# Girlfriend_Tracker_V0_2.net
KiCad netlist of a schematic drawn in EAGLE
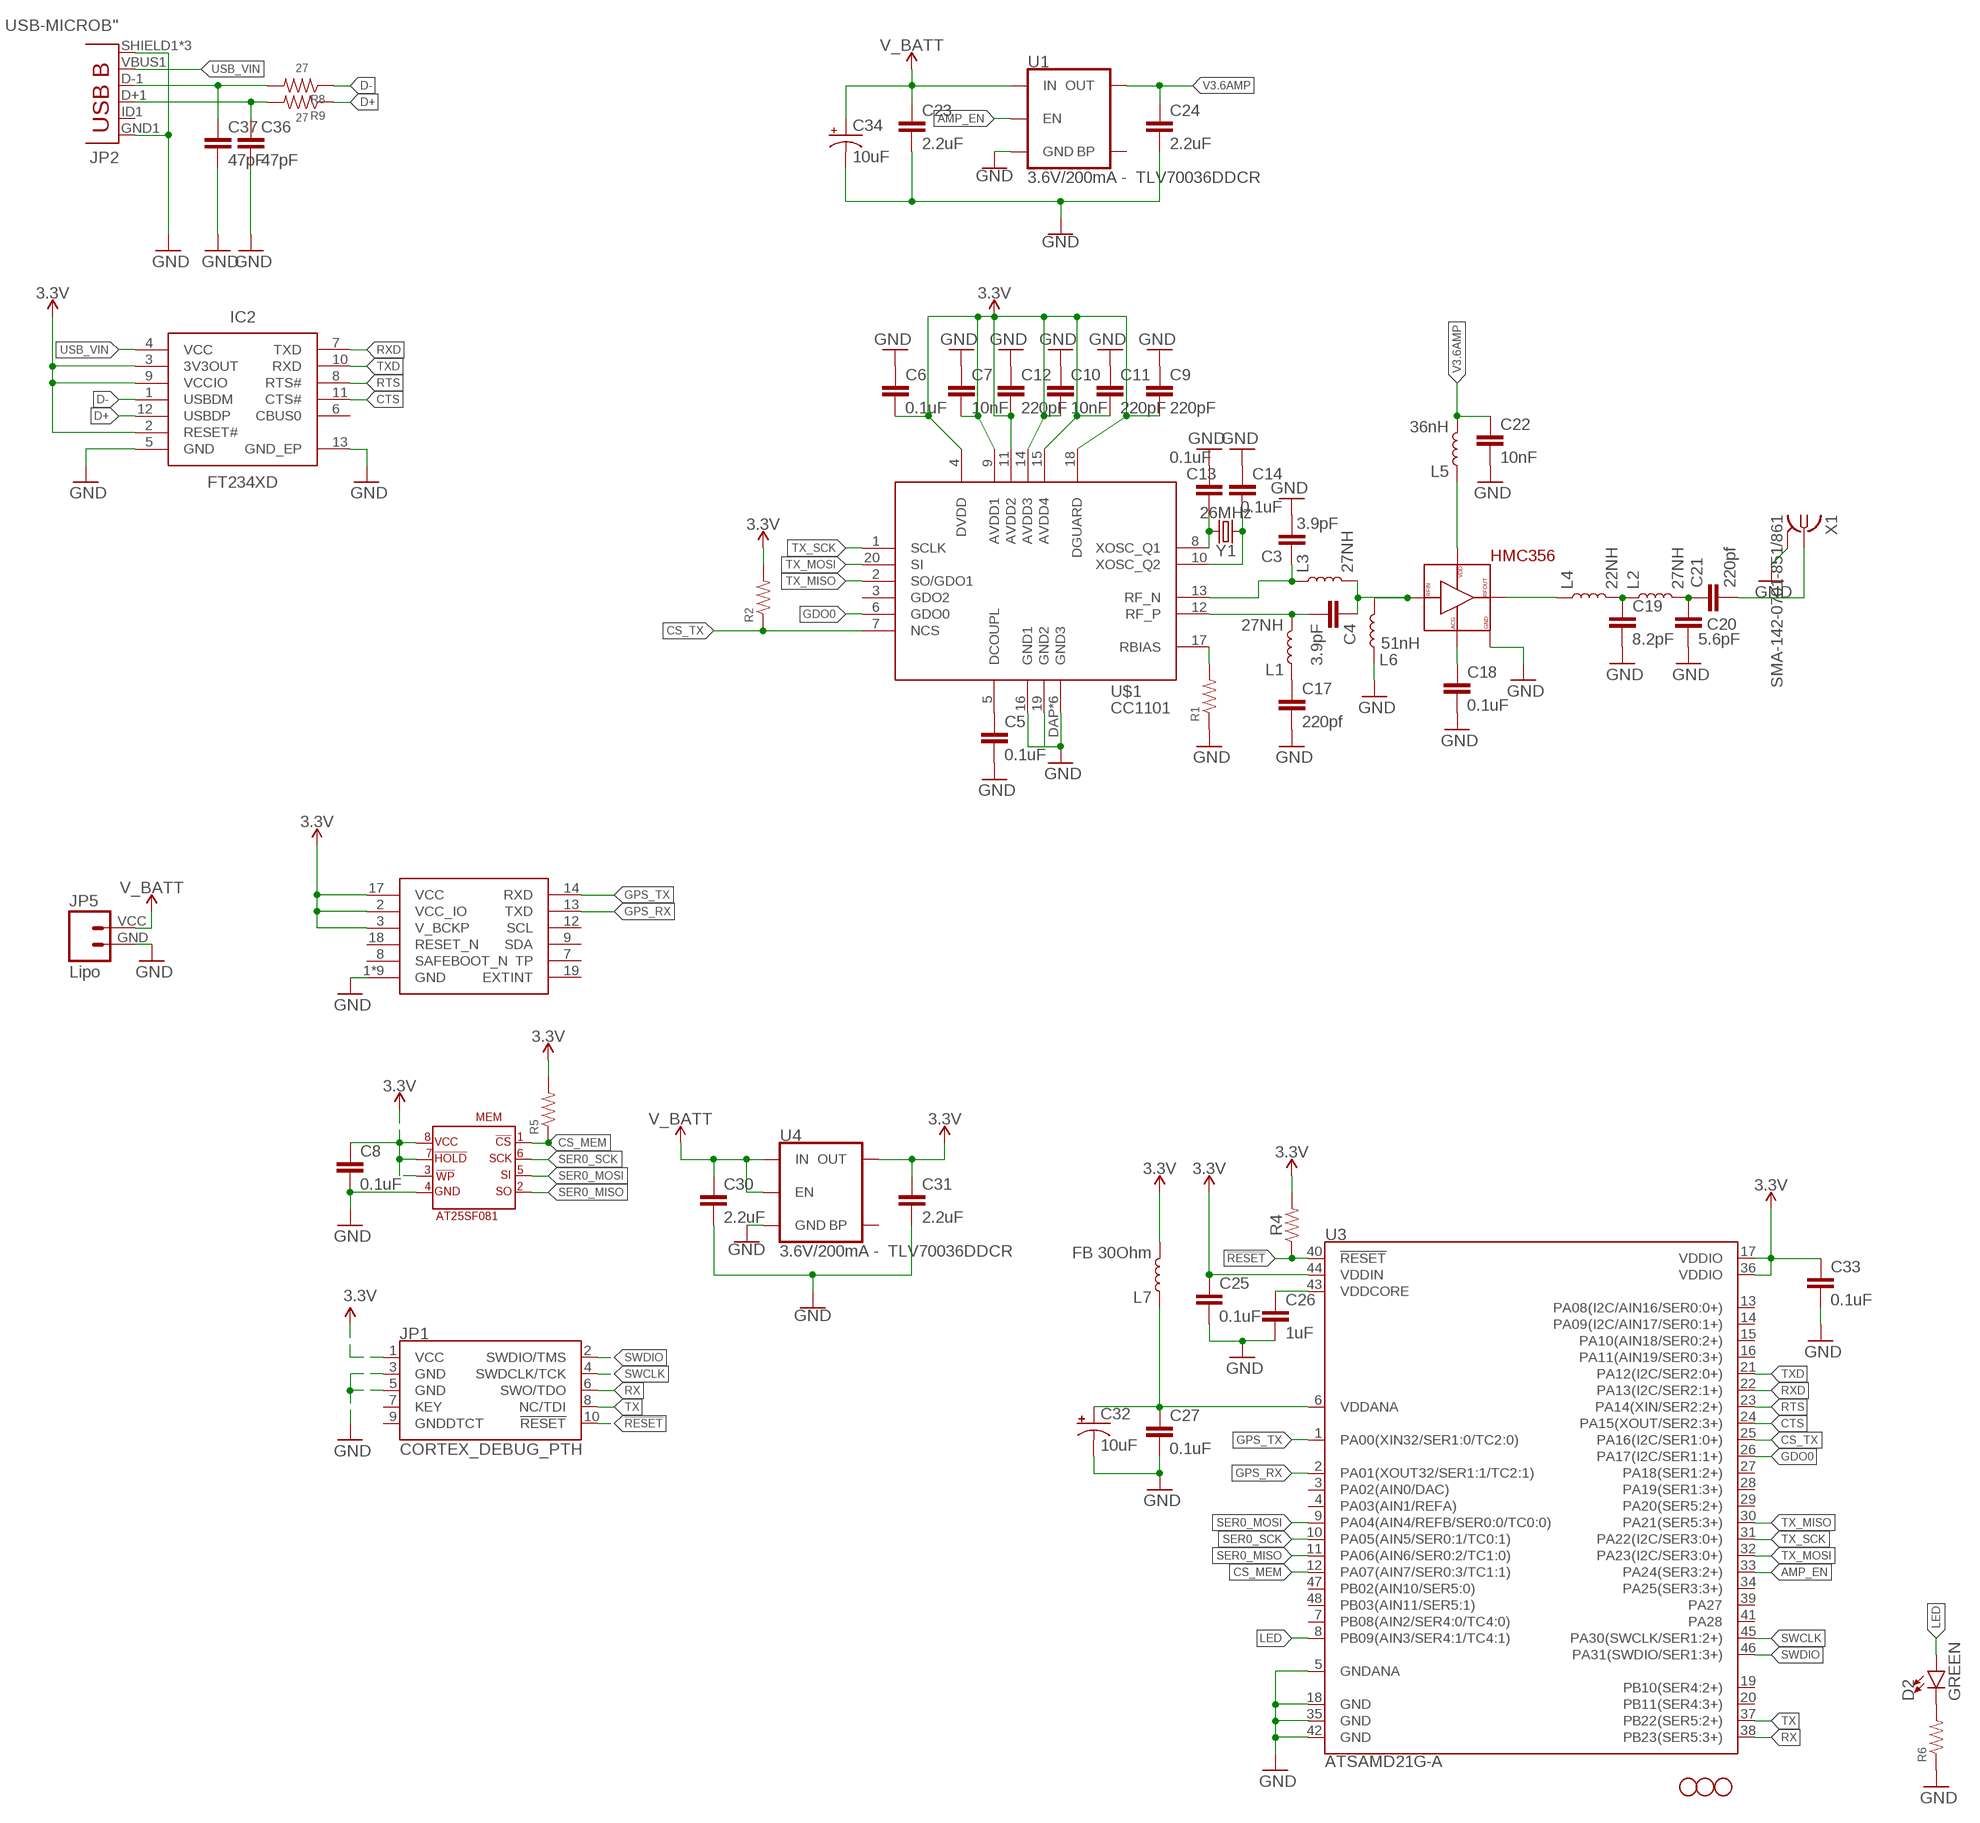
[diagram p0: schematic, sheet 1]

(export (version "E")
  (design (tool "Eeschema 10.0.6"))
  (components
    (comp (ref "C3")
      (value "3.9pF")
      (footprint "eagle-import:0402")
      (libsource (lib "eagle-import") (part "0.1UF-0402-16V-10%"))
    )
    (comp (ref "C4")
      (value "3.9pF")
      (footprint "eagle-import:0402")
      (libsource (lib "eagle-import") (part "0.1UF-0402-16V-10%"))
    )
    (comp (ref "C5")
      (value "0.1uF")
      (footprint "eagle-import:0402")
      (libsource (lib "eagle-import") (part "0.1UF-0402-16V-10%"))
    )
    (comp (ref "C6")
      (value "0.1uF")
      (footprint "eagle-import:0402")
      (libsource (lib "eagle-import") (part "0.1UF-0402-16V-10%"))
    )
    (comp (ref "C7")
      (value "10nF")
      (footprint "eagle-import:0402")
      (libsource (lib "eagle-import") (part "0.1UF-0402-16V-10%"))
    )
    (comp (ref "C8")
      (value "0.1uF")
      (footprint "eagle-import:0402")
      (libsource (lib "eagle-import") (part "0.1UF-0402-16V-10%"))
    )
    (comp (ref "C9")
      (value "220pF")
      (footprint "eagle-import:0402")
      (libsource (lib "eagle-import") (part "0.1UF-0402-16V-10%"))
    )
    (comp (ref "C10")
      (value "10nF")
      (footprint "eagle-import:0402")
      (libsource (lib "eagle-import") (part "0.1UF-0402-16V-10%"))
    )
    (comp (ref "C11")
      (value "220pF")
      (footprint "eagle-import:0402")
      (libsource (lib "eagle-import") (part "0.1UF-0402-16V-10%"))
    )
    (comp (ref "C12")
      (value "220pF")
      (footprint "eagle-import:0402")
      (libsource (lib "eagle-import") (part "0.1UF-0402-16V-10%"))
    )
    (comp (ref "C13")
      (value "0.1uF")
      (footprint "eagle-import:0402")
      (libsource (lib "eagle-import") (part "0.1UF-0402-16V-10%"))
    )
    (comp (ref "C14")
      (value "0.1uF")
      (footprint "eagle-import:0402")
      (libsource (lib "eagle-import") (part "0.1UF-0402-16V-10%"))
    )
    (comp (ref "C17")
      (value "220pf")
      (footprint "eagle-import:0402")
      (libsource (lib "eagle-import") (part "0.1UF-0402-16V-10%"))
    )
    (comp (ref "C18")
      (value "0.1uF")
      (footprint "eagle-import:0402")
      (libsource (lib "eagle-import") (part "0.1UF-0402-16V-10%"))
    )
    (comp (ref "C19")
      (value "8.2pF")
      (footprint "eagle-import:0402")
      (libsource (lib "eagle-import") (part "0.1UF-0402-16V-10%"))
    )
    (comp (ref "C20")
      (value "5.6pF")
      (footprint "eagle-import:0402")
      (libsource (lib "eagle-import") (part "0.1UF-0402-16V-10%"))
    )
    (comp (ref "C21")
      (value "220pf")
      (footprint "eagle-import:0402")
      (libsource (lib "eagle-import") (part "0.1UF-0402-16V-10%"))
    )
    (comp (ref "C22")
      (value "10nF")
      (footprint "eagle-import:0402")
      (libsource (lib "eagle-import") (part "0.1UF-0402-16V-10%"))
    )
    (comp (ref "C23")
      (value "2.2uF")
      (footprint "eagle-import:0603")
      (libsource (lib "eagle-import") (part "2.2UF-0603-10V-20%"))
    )
    (comp (ref "C24")
      (value "2.2uF")
      (footprint "eagle-import:0603")
      (libsource (lib "eagle-import") (part "2.2UF-0603-10V-20%"))
    )
    (comp (ref "C25")
      (value "0.1uF")
      (footprint "eagle-import:0402")
      (libsource (lib "eagle-import") (part "0.1UF-0402-16V-10%"))
    )
    (comp (ref "C26")
      (value "1uF")
      (footprint "eagle-import:0402")
      (libsource (lib "eagle-import") (part "0.1UF-0402-16V-10%"))
    )
    (comp (ref "C27")
      (value "0.1uF")
      (footprint "eagle-import:0402")
      (libsource (lib "eagle-import") (part "0.1UF-0402-16V-10%"))
    )
    (comp (ref "C30")
      (value "2.2uF")
      (footprint "eagle-import:0603")
      (libsource (lib "eagle-import") (part "2.2UF-0603-10V-20%"))
    )
    (comp (ref "C31")
      (value "2.2uF")
      (footprint "eagle-import:0603")
      (libsource (lib "eagle-import") (part "2.2UF-0603-10V-20%"))
    )
    (comp (ref "C32")
      (value "10uF")
      (footprint "eagle-import:EIA3216")
      (libsource (lib "eagle-import") (part "CAP_POL1206"))
    )
    (comp (ref "C33")
      (value "0.1uF")
      (footprint "eagle-import:0402")
      (libsource (lib "eagle-import") (part "0.1UF-0402-16V-10%"))
    )
    (comp (ref "C34")
      (value "10uF")
      (footprint "eagle-import:EIA3216")
      (libsource (lib "eagle-import") (part "CAP_POL1206"))
    )
    (comp (ref "C36")
      (value "47pF")
      (footprint "eagle-import:0402")
      (libsource (lib "eagle-import") (part "0.1UF-0402-16V-10%"))
    )
    (comp (ref "C37")
      (value "47pF")
      (footprint "eagle-import:0402")
      (libsource (lib "eagle-import") (part "0.1UF-0402-16V-10%"))
    )
    (comp (ref "D2")
      (value "GREEN")
      (footprint "eagle-import:LED-1206")
      (libsource (lib "eagle-import") (part "LED-GREEN1206"))
    )
    (comp (ref "H1")
      (value "STAND-OFFTIGHT")
      (footprint "eagle-import:STAND-OFF-TIGHT")
      (libsource (lib "eagle-import") (part "STAND-OFFTIGHT"))
    )
    (comp (ref "H2")
      (value "STAND-OFFTIGHT")
      (footprint "eagle-import:STAND-OFF-TIGHT")
      (libsource (lib "eagle-import") (part "STAND-OFFTIGHT"))
    )
    (comp (ref "H3")
      (value "STAND-OFFTIGHT")
      (footprint "eagle-import:STAND-OFF-TIGHT")
      (libsource (lib "eagle-import") (part "STAND-OFFTIGHT"))
    )
    (comp (ref "IC1")
      (value "SAM-M8Q")
      (footprint "eagle-import:SAM-M8Q")
      (libsource (lib "eagle-import") (part "SAM-M8Q"))
    )
    (comp (ref "IC2")
      (value "FT234XD")
      (footprint "eagle-import:SON45P300X300X80-13N")
      (fields (field (name "MANUFACTURER_PART_NUMBER") "ft234xd"))
      (libsource (lib "eagle-import") (part "FT234XD"))
    )
    (comp (ref "JP1")
      (value "CORTEX_DEBUG_PTH")
      (footprint "eagle-import:2X5-PTH-1.27MM")
      (libsource (lib "eagle-import") (part "CORTEX_DEBUG_PTH"))
    )
    (comp (ref "JP2")
      (value "USB-MICROB\"")
      (footprint "eagle-import:USB-B-MICRO-SMD_V03")
      (libsource (lib "eagle-import") (part "USB-MICROB{dblquote}"))
    )
    (comp (ref "JP5")
      (value "Lipo")
      (footprint "eagle-import:JST-2-SMD-VERT")
      (libsource (lib "eagle-import") (part "M024UCON-15767"))
    )
    (comp (ref "L1")
      (value "27NH")
      (footprint "eagle-import:0402")
      (libsource (lib "eagle-import") (part "SparkFun-Coils_512_INDUCTOR-0402-3.9NH"))
    )
    (comp (ref "L2")
      (value "27NH")
      (footprint "eagle-import:0402")
      (libsource (lib "eagle-import") (part "SparkFun-Coils_512_INDUCTOR-0402-3.9NH"))
    )
    (comp (ref "L3")
      (value "27NH")
      (footprint "eagle-import:0402")
      (libsource (lib "eagle-import") (part "SparkFun-Coils_512_INDUCTOR-0402-3.9NH"))
    )
    (comp (ref "L4")
      (value "22NH")
      (footprint "eagle-import:0402")
      (libsource (lib "eagle-import") (part "SparkFun-Coils_512_INDUCTOR-0402-3.9NH"))
    )
    (comp (ref "L5")
      (value "36nH")
      (footprint "eagle-import:0402")
      (libsource (lib "eagle-import") (part "SparkFun-Coils_512_INDUCTOR-0402-3.9NH"))
    )
    (comp (ref "L6")
      (value "51nH")
      (footprint "eagle-import:0402")
      (libsource (lib "eagle-import") (part "SparkFun-Coils_512_INDUCTOR-0402-3.9NH"))
    )
    (comp (ref "L7")
      (value "FB 30Ohm")
      (footprint "eagle-import:0603")
      (libsource (lib "eagle-import") (part "INDUCTOR-0603-33NH"))
    )
    (comp (ref "MEM")
      (value "AT25SF081")
      (footprint "eagle-import:AT25SF081")
      (libsource (lib "eagle-import") (part "AT25SF081"))
    )
    (comp (ref "R1")
      (value "RESISTOR0402")
      (footprint "eagle-import:0402")
      (libsource (lib "eagle-import") (part "RESISTOR0402"))
    )
    (comp (ref "R2")
      (value "RESISTOR0402")
      (footprint "eagle-import:0402")
      (libsource (lib "eagle-import") (part "RESISTOR0402"))
    )
    (comp (ref "R4")
      (value "RESISTOR0402")
      (footprint "eagle-import:0402")
      (libsource (lib "eagle-import") (part "RESISTOR0402"))
    )
    (comp (ref "R5")
      (value "RESISTOR0402")
      (footprint "eagle-import:0402")
      (libsource (lib "eagle-import") (part "RESISTOR0402"))
    )
    (comp (ref "R6")
      (value "RESISTOR0402")
      (footprint "eagle-import:0402")
      (libsource (lib "eagle-import") (part "RESISTOR0402"))
    )
    (comp (ref "R8")
      (value "27")
      (footprint "eagle-import:0402")
      (libsource (lib "eagle-import") (part "RESISTOR0402"))
    )
    (comp (ref "R9")
      (value "27")
      (footprint "eagle-import:0402")
      (libsource (lib "eagle-import") (part "RESISTOR0402"))
    )
    (comp (ref "U$1")
      (value "CC1101")
      (footprint "eagle-import:CC1101")
      (libsource (lib "eagle-import") (part "CC1101"))
    )
    (comp (ref "U$3")
      (value "HMC356")
      (footprint "eagle-import:QFN16_HMC356")
      (libsource (lib "eagle-import") (part "HMC356"))
    )
    (comp (ref "U1")
      (value "3.6V/200mA - TLV70036DDCR")
      (footprint "eagle-import:SOT23-5")
      (libsource (lib "eagle-import") (part "V_REG_MIC52053.3V"))
    )
    (comp (ref "U3")
      (value "ATSAMD21G-A")
      (footprint "eagle-import:TQFP-48")
      (libsource (lib "eagle-import") (part "ATSAMD21G-A"))
    )
    (comp (ref "U4")
      (value "3.6V/200mA - TLV70036DDCR")
      (footprint "eagle-import:SOT23-5")
      (libsource (lib "eagle-import") (part "V_REG_MIC52053.3V"))
    )
    (comp (ref "X1")
      (value "SMA-142-0701-851/861")
      (footprint "eagle-import:J502-ND-142-0701-851_861")
      (fields (field (name "MF") "JOHNSON COMPONENTS") (field (name "MPN") "142-0701-851"))
      (libsource (lib "eagle-import") (part "SMA-142-0701-851/861"))
    )
    (comp (ref "Y1")
      (value "26MHz")
      (footprint "eagle-import:CRYSTAL-SMD-3.2X2.5MM")
      (libsource (lib "eagle-import") (part "CRYSTALSMD-3.2X2.5"))
    )
  )
  (nets
    (net (code "1") (name "/~{RESET}") (class "Default")
      (node (ref "JP1") (pin "10") (pinfunction "~{RESET}_10") (pintype "bidirectional"))
      (node (ref "R4") (pin "1") (pinfunction "1_1") (pintype "passive"))
      (node (ref "U3") (pin "40") (pinfunction "~{RESET}_40") (pintype "bidirectional"))
    )
    (net (code "2") (name "3.3V") (class "Default")
      (node (ref "C10") (pin "2") (pinfunction "2_2") (pintype "passive"))
      (node (ref "C11") (pin "2") (pinfunction "2_2") (pintype "passive"))
      (node (ref "C12") (pin "2") (pinfunction "2_2") (pintype "passive"))
      (node (ref "C25") (pin "1") (pinfunction "1_1") (pintype "passive"))
      (node (ref "C31") (pin "1") (pinfunction "1_1") (pintype "passive"))
      (node (ref "C33") (pin "1") (pinfunction "1_1") (pintype "passive"))
      (node (ref "C6") (pin "2") (pinfunction "2_2") (pintype "passive"))
      (node (ref "C7") (pin "2") (pinfunction "2_2") (pintype "passive"))
      (node (ref "C8") (pin "1") (pinfunction "1_1") (pintype "passive"))
      (node (ref "C9") (pin "2") (pinfunction "2_2") (pintype "passive"))
      (node (ref "IC1") (pin "17") (pinfunction "VCC_17") (pintype "bidirectional"))
      (node (ref "IC1") (pin "2") (pinfunction "VCC_IO_2") (pintype "bidirectional"))
      (node (ref "IC1") (pin "3") (pinfunction "V_BCKP_3") (pintype "bidirectional"))
      (node (ref "IC2") (pin "2") (pinfunction "RESET#_2") (pintype "passive"))
      (node (ref "IC2") (pin "3") (pinfunction "3V3OUT_3") (pintype "output"))
      (node (ref "IC2") (pin "9") (pinfunction "VCCIO_9") (pintype "power_in"))
      (node (ref "JP1") (pin "1") (pinfunction "VCC_1") (pintype "bidirectional"))
      (node (ref "L7") (pin "2") (pinfunction "2_2") (pintype "passive"))
      (node (ref "MEM") (pin "!HOLD") (pinfunction "~{HOLD}_!HOLD") (pintype "bidirectional"))
      (node (ref "MEM") (pin "!WP") (pinfunction "~{WP}_!WP") (pintype "bidirectional"))
      (node (ref "MEM") (pin "VCC") (pinfunction "VCC_VCC") (pintype "bidirectional"))
      (node (ref "R2") (pin "2") (pinfunction "2_2") (pintype "passive"))
      (node (ref "R4") (pin "2") (pinfunction "2_2") (pintype "passive"))
      (node (ref "R5") (pin "2") (pinfunction "2_2") (pintype "passive"))
      (node (ref "U$1") (pin "11") (pinfunction "AVDD2_11") (pintype "bidirectional"))
      (node (ref "U$1") (pin "14") (pinfunction "AVDD3_14") (pintype "bidirectional"))
      (node (ref "U$1") (pin "15") (pinfunction "AVDD4_15") (pintype "bidirectional"))
      (node (ref "U$1") (pin "18") (pinfunction "DGUARD_18") (pintype "bidirectional"))
      (node (ref "U$1") (pin "4") (pinfunction "DVDD_4") (pintype "bidirectional"))
      (node (ref "U$1") (pin "9") (pinfunction "AVDD1_9") (pintype "bidirectional"))
      (node (ref "U3") (pin "17") (pinfunction "VDDIO_17") (pintype "bidirectional"))
      (node (ref "U3") (pin "36") (pinfunction "VDDIO_36") (pintype "bidirectional"))
      (node (ref "U3") (pin "44") (pinfunction "VDDIN_44") (pintype "bidirectional"))
      (node (ref "U4") (pin "5") (pinfunction "OUT_5") (pintype "passive"))
    )
    (net (code "3") (name "AMP_EN") (class "Default")
      (node (ref "U1") (pin "3") (pinfunction "EN_3") (pintype "input"))
      (node (ref "U3") (pin "33") (pinfunction "PA24(SER3:2+)_33") (pintype "bidirectional"))
    )
    (net (code "4") (name "CS_MEM") (class "Default")
      (node (ref "MEM") (pin "!CS") (pinfunction "~{CS}_!CS") (pintype "bidirectional"))
      (node (ref "R5") (pin "1") (pinfunction "1_1") (pintype "passive"))
      (node (ref "U3") (pin "12") (pinfunction "PA07(AIN7/SER0:3/TC1:1)_12") (pintype "bidirectional"))
    )
    (net (code "5") (name "CS_TX") (class "Default")
      (node (ref "R2") (pin "1") (pinfunction "1_1") (pintype "passive"))
      (node (ref "U$1") (pin "7") (pinfunction "NCS_7") (pintype "bidirectional"))
      (node (ref "U3") (pin "25") (pinfunction "PA16(I2C/SER1:0+)_25") (pintype "bidirectional"))
    )
    (net (code "6") (name "CTS") (class "Default")
      (node (ref "IC2") (pin "11") (pinfunction "CTS#_11") (pintype "passive"))
      (node (ref "U3") (pin "24") (pinfunction "PA15(XOUT/SER2:3+)_24") (pintype "bidirectional"))
    )
    (net (code "7") (name "D+") (class "Default")
      (node (ref "IC2") (pin "12") (pinfunction "USBDP_12") (pintype "passive"))
      (node (ref "R9") (pin "1") (pinfunction "1_1") (pintype "passive"))
    )
    (net (code "8") (name "D-") (class "Default")
      (node (ref "IC2") (pin "1") (pinfunction "USBDM_1") (pintype "passive"))
      (node (ref "R8") (pin "1") (pinfunction "1_1") (pintype "passive"))
    )
    (net (code "9") (name "GDO0") (class "Default")
      (node (ref "U$1") (pin "6") (pinfunction "GDO0_6") (pintype "bidirectional"))
      (node (ref "U3") (pin "26") (pinfunction "PA17(I2C/SER1:1+)_26") (pintype "bidirectional"))
    )
    (net (code "10") (name "GND") (class "Default")
      (node (ref "C10") (pin "1") (pinfunction "1_1") (pintype "passive"))
      (node (ref "C11") (pin "1") (pinfunction "1_1") (pintype "passive"))
      (node (ref "C12") (pin "1") (pinfunction "1_1") (pintype "passive"))
      (node (ref "C13") (pin "1") (pinfunction "1_1") (pintype "passive"))
      (node (ref "C14") (pin "2") (pinfunction "2_2") (pintype "passive"))
      (node (ref "C17") (pin "2") (pinfunction "2_2") (pintype "passive"))
      (node (ref "C18") (pin "2") (pinfunction "2_2") (pintype "passive"))
      (node (ref "C19") (pin "2") (pinfunction "2_2") (pintype "passive"))
      (node (ref "C20") (pin "2") (pinfunction "2_2") (pintype "passive"))
      (node (ref "C22") (pin "2") (pinfunction "2_2") (pintype "passive"))
      (node (ref "C23") (pin "2") (pinfunction "2_2") (pintype "passive"))
      (node (ref "C24") (pin "2") (pinfunction "2_2") (pintype "passive"))
      (node (ref "C25") (pin "2") (pinfunction "2_2") (pintype "passive"))
      (node (ref "C26") (pin "2") (pinfunction "2_2") (pintype "passive"))
      (node (ref "C27") (pin "2") (pinfunction "2_2") (pintype "passive"))
      (node (ref "C3") (pin "2") (pinfunction "2_2") (pintype "passive"))
      (node (ref "C30") (pin "2") (pinfunction "2_2") (pintype "passive"))
      (node (ref "C31") (pin "2") (pinfunction "2_2") (pintype "passive"))
      (node (ref "C32") (pin "C") (pinfunction "-_C") (pintype "passive"))
      (node (ref "C33") (pin "2") (pinfunction "2_2") (pintype "passive"))
      (node (ref "C34") (pin "C") (pinfunction "-_C") (pintype "passive"))
      (node (ref "C36") (pin "2") (pinfunction "2_2") (pintype "passive"))
      (node (ref "C37") (pin "2") (pinfunction "2_2") (pintype "passive"))
      (node (ref "C5") (pin "2") (pinfunction "2_2") (pintype "passive"))
      (node (ref "C6") (pin "1") (pinfunction "1_1") (pintype "passive"))
      (node (ref "C7") (pin "1") (pinfunction "1_1") (pintype "passive"))
      (node (ref "C8") (pin "2") (pinfunction "2_2") (pintype "passive"))
      (node (ref "C9") (pin "1") (pinfunction "1_1") (pintype "passive"))
      (node (ref "IC1") (pin "1") (pinfunction "GND_1") (pintype "bidirectional"))
      (node (ref "IC1") (pin "10") (pinfunction "GND_10") (pintype "bidirectional"))
      (node (ref "IC1") (pin "11") (pinfunction "GND_11") (pintype "bidirectional"))
      (node (ref "IC1") (pin "15") (pinfunction "GND_15") (pintype "bidirectional"))
      (node (ref "IC1") (pin "16") (pinfunction "GND_16") (pintype "bidirectional"))
      (node (ref "IC1") (pin "20") (pinfunction "GND_20") (pintype "bidirectional"))
      (node (ref "IC1") (pin "4") (pinfunction "GND_4") (pintype "bidirectional"))
      (node (ref "IC1") (pin "5") (pinfunction "GND_5") (pintype "bidirectional"))
      (node (ref "IC1") (pin "6") (pinfunction "GND_6") (pintype "bidirectional"))
      (node (ref "IC2") (pin "13") (pinfunction "GND_EP_13") (pintype "power_in"))
      (node (ref "IC2") (pin "5") (pinfunction "GND_5") (pintype "power_in"))
      (node (ref "JP1") (pin "3") (pinfunction "GND_3") (pintype "bidirectional"))
      (node (ref "JP1") (pin "5") (pinfunction "GND_5") (pintype "bidirectional"))
      (node (ref "JP2") (pin "GND1") (pinfunction "GND_GND1") (pintype "bidirectional"))
      (node (ref "JP2") (pin "SHIELD1") (pinfunction "SHIELD_SHIELD1") (pintype "bidirectional"))
      (node (ref "JP2") (pin "SHIELD2") (pinfunction "SHIELD_SHIELD2") (pintype "bidirectional"))
      (node (ref "JP2") (pin "SHIELD3") (pinfunction "SHIELD_SHIELD3") (pintype "bidirectional"))
      (node (ref "JP5") (pin "GND") (pinfunction "1_GND") (pintype "passive"))
      (node (ref "L6") (pin "1") (pinfunction "1_1") (pintype "passive"))
      (node (ref "MEM") (pin "GND") (pinfunction "GND_GND") (pintype "bidirectional"))
      (node (ref "R1") (pin "1") (pinfunction "1_1") (pintype "passive"))
      (node (ref "R6") (pin "1") (pinfunction "1_1") (pintype "passive"))
      (node (ref "U$1") (pin "16") (pinfunction "GND1_16") (pintype "bidirectional"))
      (node (ref "U$1") (pin "19") (pinfunction "GND2_19") (pintype "bidirectional"))
      (node (ref "U$1") (pin "DAP") (pinfunction "GND3_DAP") (pintype "bidirectional"))
      (node (ref "U$1") (pin "P$1") (pinfunction "GND3_P$1") (pintype "bidirectional"))
      (node (ref "U$1") (pin "P$2") (pinfunction "GND3_P$2") (pintype "bidirectional"))
      (node (ref "U$1") (pin "P$3") (pinfunction "GND3_P$3") (pintype "bidirectional"))
      (node (ref "U$1") (pin "P$4") (pinfunction "GND3_P$4") (pintype "bidirectional"))
      (node (ref "U$1") (pin "P$5") (pinfunction "GND3_P$5") (pintype "bidirectional"))
      (node (ref "U$3") (pin "P$16") (pinfunction "P$5_P$16") (pintype "bidirectional"))
      (node (ref "U$3") (pin "P$17") (pinfunction "P$5_P$17") (pintype "bidirectional"))
      (node (ref "U$3") (pin "P$17_1") (pinfunction "P$5_P$17_1") (pintype "bidirectional"))
      (node (ref "U$3") (pin "P$17_2") (pinfunction "P$5_P$17_2") (pintype "bidirectional"))
      (node (ref "U$3") (pin "P$17_3") (pinfunction "P$5_P$17_3") (pintype "bidirectional"))
      (node (ref "U$3") (pin "P$17_4") (pinfunction "P$5_P$17_4") (pintype "bidirectional"))
      (node (ref "U$3") (pin "P$2") (pinfunction "P$5_P$2") (pintype "bidirectional"))
      (node (ref "U$3") (pin "P$4") (pinfunction "P$5_P$4") (pintype "bidirectional"))
      (node (ref "U$3") (pin "P$6") (pinfunction "P$5_P$6") (pintype "bidirectional"))
      (node (ref "U1") (pin "2") (pinfunction "GND_2") (pintype "input"))
      (node (ref "U3") (pin "18") (pinfunction "GND_18") (pintype "bidirectional"))
      (node (ref "U3") (pin "35") (pinfunction "GND_35") (pintype "bidirectional"))
      (node (ref "U3") (pin "42") (pinfunction "GND_42") (pintype "bidirectional"))
      (node (ref "U3") (pin "5") (pinfunction "GNDANA_5") (pintype "bidirectional"))
      (node (ref "U4") (pin "2") (pinfunction "GND_2") (pintype "input"))
      (node (ref "X1") (pin "G@1") (pinfunction "2_G@1") (pintype "passive"))
      (node (ref "X1") (pin "G@2") (pinfunction "2_G@2") (pintype "passive"))
      (node (ref "X1") (pin "G@3") (pinfunction "2_G@3") (pintype "passive"))
      (node (ref "X1") (pin "G@4") (pinfunction "2_G@4") (pintype "passive"))
    )
    (net (code "11") (name "GPS_RX") (class "Default")
      (node (ref "IC1") (pin "13") (pinfunction "TXD_13") (pintype "bidirectional"))
      (node (ref "U3") (pin "2") (pinfunction "PA01(XOUT32/SER1:1/TC2:1)_2") (pintype "bidirectional"))
    )
    (net (code "12") (name "GPS_TX") (class "Default")
      (node (ref "IC1") (pin "14") (pinfunction "RXD_14") (pintype "bidirectional"))
      (node (ref "U3") (pin "1") (pinfunction "PA00(XIN32/SER1:0/TC2:0)_1") (pintype "bidirectional"))
    )
    (net (code "13") (name "LED") (class "Default")
      (node (ref "D2") (pin "A") (pinfunction "A_A") (pintype "passive"))
      (node (ref "U3") (pin "8") (pinfunction "PB09(AIN3/SER4:1/TC4:1)_8") (pintype "bidirectional"))
    )
    (net (code "14") (name "Net-(C17-Pad1)") (class "Default")
      (node (ref "C17") (pin "1") (pinfunction "1_1") (pintype "passive"))
      (node (ref "L1") (pin "1") (pinfunction "1_1") (pintype "passive"))
    )
    (net (code "15") (name "Net-(C19-Pad1)") (class "Default")
      (node (ref "C19") (pin "1") (pinfunction "1_1") (pintype "passive"))
      (node (ref "L2") (pin "1") (pinfunction "1_1") (pintype "passive"))
      (node (ref "L4") (pin "2") (pinfunction "2_2") (pintype "passive"))
    )
    (net (code "16") (name "Net-(C20-Pad1)") (class "Default")
      (node (ref "C20") (pin "1") (pinfunction "1_1") (pintype "passive"))
      (node (ref "C21") (pin "1") (pinfunction "1_1") (pintype "passive"))
      (node (ref "L2") (pin "2") (pinfunction "2_2") (pintype "passive"))
    )
    (net (code "17") (name "Net-(C21-Pad2)") (class "Default")
      (node (ref "C21") (pin "2") (pinfunction "2_2") (pintype "passive"))
      (node (ref "X1") (pin "1") (pinfunction "1_1") (pintype "passive"))
    )
    (net (code "18") (name "Net-(C32-+)") (class "Default")
      (node (ref "C27") (pin "1") (pinfunction "1_1") (pintype "passive"))
      (node (ref "C32") (pin "A") (pinfunction "+_A") (pintype "passive"))
      (node (ref "L7") (pin "1") (pinfunction "1_1") (pintype "passive"))
      (node (ref "U3") (pin "6") (pinfunction "VDDANA_6") (pintype "bidirectional"))
    )
    (net (code "19") (name "Net-(D2-PadC)") (class "Default")
      (node (ref "D2") (pin "C") (pinfunction "C_C") (pintype "passive"))
      (node (ref "R6") (pin "2") (pinfunction "2_2") (pintype "passive"))
    )
    (net (code "20") (name "Net-(JP2-D+)") (class "Default")
      (node (ref "C36") (pin "1") (pinfunction "1_1") (pintype "passive"))
      (node (ref "JP2") (pin "D+1") (pinfunction "D+_D+1") (pintype "bidirectional"))
      (node (ref "R9") (pin "2") (pinfunction "2_2") (pintype "passive"))
    )
    (net (code "21") (name "Net-(JP2-D-)") (class "Default")
      (node (ref "C37") (pin "1") (pinfunction "1_1") (pintype "passive"))
      (node (ref "JP2") (pin "D-1") (pinfunction "D-_D-1") (pintype "bidirectional"))
      (node (ref "R8") (pin "2") (pinfunction "2_2") (pintype "passive"))
    )
    (net (code "22") (name "Net-(U$1-DCOUPL)") (class "Default")
      (node (ref "C5") (pin "1") (pinfunction "1_1") (pintype "passive"))
      (node (ref "U$1") (pin "5") (pinfunction "DCOUPL_5") (pintype "bidirectional"))
    )
    (net (code "23") (name "Net-(U$1-RBIAS)") (class "Default")
      (node (ref "R1") (pin "2") (pinfunction "2_2") (pintype "passive"))
      (node (ref "U$1") (pin "17") (pinfunction "RBIAS_17") (pintype "bidirectional"))
    )
    (net (code "24") (name "Net-(U$1-RF_N)") (class "Default")
      (node (ref "C3") (pin "1") (pinfunction "1_1") (pintype "passive"))
      (node (ref "L3") (pin "1") (pinfunction "1_1") (pintype "passive"))
      (node (ref "U$1") (pin "13") (pinfunction "RF_N_13") (pintype "bidirectional"))
    )
    (net (code "25") (name "Net-(U$1-RF_P)") (class "Default")
      (node (ref "C4") (pin "2") (pinfunction "2_2") (pintype "passive"))
      (node (ref "L1") (pin "2") (pinfunction "2_2") (pintype "passive"))
      (node (ref "U$1") (pin "12") (pinfunction "RF_P_12") (pintype "bidirectional"))
    )
    (net (code "26") (name "Net-(U$1-XOSC_Q1)") (class "Default")
      (node (ref "C13") (pin "2") (pinfunction "2_2") (pintype "passive"))
      (node (ref "U$1") (pin "8") (pinfunction "XOSC_Q1_8") (pintype "bidirectional"))
      (node (ref "Y1") (pin "3") (pinfunction "2_3") (pintype "passive"))
    )
    (net (code "27") (name "Net-(U$1-XOSC_Q2)") (class "Default")
      (node (ref "C14") (pin "1") (pinfunction "1_1") (pintype "passive"))
      (node (ref "U$1") (pin "10") (pinfunction "XOSC_Q2_10") (pintype "bidirectional"))
      (node (ref "Y1") (pin "1") (pinfunction "1_1") (pintype "passive"))
    )
    (net (code "28") (name "Net-(U$3-P$1)") (class "Default")
      (node (ref "C4") (pin "1") (pinfunction "1_1") (pintype "passive"))
      (node (ref "L3") (pin "2") (pinfunction "2_2") (pintype "passive"))
      (node (ref "L6") (pin "2") (pinfunction "2_2") (pintype "passive"))
      (node (ref "U$3") (pin "P$3") (pinfunction "P$1_P$3") (pintype "bidirectional"))
    )
    (net (code "29") (name "Net-(U$3-P$2)") (class "Default")
      (node (ref "L4") (pin "1") (pinfunction "1_1") (pintype "passive"))
      (node (ref "U$3") (pin "P$11") (pinfunction "P$2_P$11") (pintype "bidirectional"))
    )
    (net (code "30") (name "Net-(U$3-P$3)") (class "Default")
      (node (ref "C18") (pin "1") (pinfunction "1_1") (pintype "passive"))
      (node (ref "U$3") (pin "P$7") (pinfunction "P$3_P$7") (pintype "bidirectional"))
    )
    (net (code "31") (name "Net-(U$3-P$4)") (class "Default")
      (node (ref "L5") (pin "1") (pinfunction "1_1") (pintype "passive"))
      (node (ref "U$3") (pin "P$15") (pinfunction "P$4_P$15") (pintype "bidirectional"))
    )
    (net (code "32") (name "Net-(U3-VDDCORE)") (class "Default")
      (node (ref "C26") (pin "1") (pinfunction "1_1") (pintype "passive"))
      (node (ref "U3") (pin "43") (pinfunction "VDDCORE_43") (pintype "bidirectional"))
    )
    (net (code "33") (name "RTS") (class "Default")
      (node (ref "IC2") (pin "8") (pinfunction "RTS#_8") (pintype "passive"))
      (node (ref "U3") (pin "23") (pinfunction "PA14(XIN/SER2:2+)_23") (pintype "bidirectional"))
    )
    (net (code "34") (name "RX") (class "Default")
      (node (ref "JP1") (pin "6") (pinfunction "SWO/TDO_6") (pintype "bidirectional"))
      (node (ref "U3") (pin "38") (pinfunction "PB23(SER5:3+)_38") (pintype "bidirectional"))
    )
    (net (code "35") (name "RXD") (class "Default")
      (node (ref "IC2") (pin "7") (pinfunction "TXD_7") (pintype "passive"))
      (node (ref "U3") (pin "22") (pinfunction "PA13(I2C/SER2:1+)_22") (pintype "bidirectional"))
    )
    (net (code "36") (name "SER0_MISO") (class "Default")
      (node (ref "MEM") (pin "SO") (pinfunction "SO_SO") (pintype "bidirectional"))
      (node (ref "U3") (pin "11") (pinfunction "PA06(AIN6/SER0:2/TC1:0)_11") (pintype "bidirectional"))
    )
    (net (code "37") (name "SER0_MOSI") (class "Default")
      (node (ref "MEM") (pin "SI") (pinfunction "SI_SI") (pintype "bidirectional"))
      (node (ref "U3") (pin "9") (pinfunction "PA04(AIN4/REFB/SER0:0/TC0:0)_9") (pintype "bidirectional"))
    )
    (net (code "38") (name "SER0_SCK") (class "Default")
      (node (ref "MEM") (pin "SCK") (pinfunction "SCK_SCK") (pintype "bidirectional"))
      (node (ref "U3") (pin "10") (pinfunction "PA05(AIN5/SER0:1/TC0:1)_10") (pintype "bidirectional"))
    )
    (net (code "39") (name "SWCLK") (class "Default")
      (node (ref "JP1") (pin "4") (pinfunction "SWDCLK/TCK_4") (pintype "bidirectional"))
      (node (ref "U3") (pin "45") (pinfunction "PA30(SWCLK/SER1:2+)_45") (pintype "bidirectional"))
    )
    (net (code "40") (name "SWDIO") (class "Default")
      (node (ref "JP1") (pin "2") (pinfunction "SWDIO/TMS_2") (pintype "bidirectional"))
      (node (ref "U3") (pin "46") (pinfunction "PA31(SWDIO/SER1:3+)_46") (pintype "bidirectional"))
    )
    (net (code "41") (name "TX") (class "Default")
      (node (ref "JP1") (pin "8") (pinfunction "NC/TDI_8") (pintype "bidirectional"))
      (node (ref "U3") (pin "37") (pinfunction "PB22(SER5:2+)_37") (pintype "bidirectional"))
    )
    (net (code "42") (name "TXD") (class "Default")
      (node (ref "IC2") (pin "10") (pinfunction "RXD_10") (pintype "passive"))
      (node (ref "U3") (pin "21") (pinfunction "PA12(I2C/SER2:0+)_21") (pintype "bidirectional"))
    )
    (net (code "43") (name "TX_MISO") (class "Default")
      (node (ref "U$1") (pin "2") (pinfunction "SO/GDO1_2") (pintype "bidirectional"))
      (node (ref "U3") (pin "30") (pinfunction "PA21(SER5:3+)_30") (pintype "bidirectional"))
    )
    (net (code "44") (name "TX_MOSI") (class "Default")
      (node (ref "U$1") (pin "20") (pinfunction "SI_20") (pintype "bidirectional"))
      (node (ref "U3") (pin "32") (pinfunction "PA23(I2C/SER3:0+)_32") (pintype "bidirectional"))
    )
    (net (code "45") (name "TX_SCK") (class "Default")
      (node (ref "U$1") (pin "1") (pinfunction "SCLK_1") (pintype "bidirectional"))
      (node (ref "U3") (pin "31") (pinfunction "PA22(I2C/SER3:0+)_31") (pintype "bidirectional"))
    )
    (net (code "46") (name "USB_VIN") (class "Default")
      (node (ref "IC2") (pin "4") (pinfunction "VCC_4") (pintype "power_in"))
      (node (ref "JP2") (pin "VBUS1") (pinfunction "VBUS_VBUS1") (pintype "bidirectional"))
    )
    (net (code "47") (name "V3.6AMP") (class "Default")
      (node (ref "C22") (pin "1") (pinfunction "1_1") (pintype "passive"))
      (node (ref "C24") (pin "1") (pinfunction "1_1") (pintype "passive"))
      (node (ref "L5") (pin "2") (pinfunction "2_2") (pintype "passive"))
      (node (ref "U1") (pin "5") (pinfunction "OUT_5") (pintype "passive"))
    )
    (net (code "48") (name "V_BATT") (class "Default")
      (node (ref "C23") (pin "1") (pinfunction "1_1") (pintype "passive"))
      (node (ref "C30") (pin "1") (pinfunction "1_1") (pintype "passive"))
      (node (ref "C34") (pin "A") (pinfunction "+_A") (pintype "passive"))
      (node (ref "JP5") (pin "VCC") (pinfunction "2_VCC") (pintype "passive"))
      (node (ref "U1") (pin "1") (pinfunction "IN_1") (pintype "input"))
      (node (ref "U4") (pin "1") (pinfunction "IN_1") (pintype "input"))
      (node (ref "U4") (pin "3") (pinfunction "EN_3") (pintype "input"))
    )
    (net (code "49") (name "unconnected-(IC1-EXTINT-Pad19)") (class "Default")
      (node (ref "IC1") (pin "19") (pinfunction "EXTINT_19") (pintype "bidirectional"))
    )
    (net (code "50") (name "unconnected-(IC1-RESET_N-Pad18)") (class "Default")
      (node (ref "IC1") (pin "18") (pinfunction "RESET_N_18") (pintype "bidirectional"))
    )
    (net (code "51") (name "unconnected-(IC1-SAFEBOOT_N-Pad8)") (class "Default")
      (node (ref "IC1") (pin "8") (pinfunction "SAFEBOOT_N_8") (pintype "bidirectional"))
    )
    (net (code "52") (name "unconnected-(IC1-SCL-Pad12)") (class "Default")
      (node (ref "IC1") (pin "12") (pinfunction "SCL_12") (pintype "bidirectional"))
    )
    (net (code "53") (name "unconnected-(IC1-SDA-Pad9)") (class "Default")
      (node (ref "IC1") (pin "9") (pinfunction "SDA_9") (pintype "bidirectional"))
    )
    (net (code "54") (name "unconnected-(IC1-TP-Pad7)") (class "Default")
      (node (ref "IC1") (pin "7") (pinfunction "TP_7") (pintype "bidirectional"))
    )
    (net (code "55") (name "unconnected-(IC2-CBUS0-Pad6)") (class "Default")
      (node (ref "IC2") (pin "6") (pinfunction "CBUS0_6") (pintype "passive"))
    )
    (net (code "56") (name "unconnected-(JP1-GNDDTCT-Pad9)") (class "Default")
      (node (ref "JP1") (pin "9") (pinfunction "GNDDTCT_9") (pintype "bidirectional"))
    )
    (net (code "57") (name "unconnected-(JP1-KEY-Pad7)") (class "Default")
      (node (ref "JP1") (pin "7") (pinfunction "KEY_7") (pintype "bidirectional"))
    )
    (net (code "58") (name "unconnected-(JP2-USBID-PadID1)") (class "Default")
      (node (ref "JP2") (pin "ID1") (pinfunction "USBID_ID1") (pintype "bidirectional"))
    )
    (net (code "59") (name "unconnected-(U$1-GDO2-Pad3)") (class "Default")
      (node (ref "U$1") (pin "3") (pinfunction "GDO2_3") (pintype "bidirectional"))
    )
    (net (code "60") (name "unconnected-(U1-BP-Pad4)") (class "Default")
      (node (ref "U1") (pin "4") (pinfunction "BP_4") (pintype "input"))
    )
    (net (code "61") (name "unconnected-(U3-PA02(AIN0{slash}DAC)-Pad3)") (class "Default")
      (node (ref "U3") (pin "3") (pinfunction "PA02(AIN0/DAC)_3") (pintype "bidirectional"))
    )
    (net (code "62") (name "unconnected-(U3-PA03(AIN1{slash}REFA)-Pad4)") (class "Default")
      (node (ref "U3") (pin "4") (pinfunction "PA03(AIN1/REFA)_4") (pintype "bidirectional"))
    )
    (net (code "63") (name "unconnected-(U3-PA08(I2C{slash}AIN16{slash}SER0:0+)-Pad13)") (class "Default")
      (node (ref "U3") (pin "13") (pinfunction "PA08(I2C/AIN16/SER0:0+)_13") (pintype "bidirectional"))
    )
    (net (code "64") (name "unconnected-(U3-PA09(I2C{slash}AIN17{slash}SER0:1+)-Pad14)") (class "Default")
      (node (ref "U3") (pin "14") (pinfunction "PA09(I2C/AIN17/SER0:1+)_14") (pintype "bidirectional"))
    )
    (net (code "65") (name "unconnected-(U3-PA10(AIN18{slash}SER0:2+)-Pad15)") (class "Default")
      (node (ref "U3") (pin "15") (pinfunction "PA10(AIN18/SER0:2+)_15") (pintype "bidirectional"))
    )
    (net (code "66") (name "unconnected-(U3-PA11(AIN19{slash}SER0:3+)-Pad16)") (class "Default")
      (node (ref "U3") (pin "16") (pinfunction "PA11(AIN19/SER0:3+)_16") (pintype "bidirectional"))
    )
    (net (code "67") (name "unconnected-(U3-PA18(SER1:2+)-Pad27)") (class "Default")
      (node (ref "U3") (pin "27") (pinfunction "PA18(SER1:2+)_27") (pintype "bidirectional"))
    )
    (net (code "68") (name "unconnected-(U3-PA19(SER1:3+)-Pad28)") (class "Default")
      (node (ref "U3") (pin "28") (pinfunction "PA19(SER1:3+)_28") (pintype "bidirectional"))
    )
    (net (code "69") (name "unconnected-(U3-PA20(SER5:2+)-Pad29)") (class "Default")
      (node (ref "U3") (pin "29") (pinfunction "PA20(SER5:2+)_29") (pintype "bidirectional"))
    )
    (net (code "70") (name "unconnected-(U3-PA25(SER3:3+)-Pad34)") (class "Default")
      (node (ref "U3") (pin "34") (pinfunction "PA25(SER3:3+)_34") (pintype "bidirectional"))
    )
    (net (code "71") (name "unconnected-(U3-PA27-Pad39)") (class "Default")
      (node (ref "U3") (pin "39") (pinfunction "PA27_39") (pintype "bidirectional"))
    )
    (net (code "72") (name "unconnected-(U3-PA28-Pad41)") (class "Default")
      (node (ref "U3") (pin "41") (pinfunction "PA28_41") (pintype "bidirectional"))
    )
    (net (code "73") (name "unconnected-(U3-PB02(AIN10{slash}SER5:0)-Pad47)") (class "Default")
      (node (ref "U3") (pin "47") (pinfunction "PB02(AIN10/SER5:0)_47") (pintype "bidirectional"))
    )
    (net (code "74") (name "unconnected-(U3-PB03(AIN11{slash}SER5:1)-Pad48)") (class "Default")
      (node (ref "U3") (pin "48") (pinfunction "PB03(AIN11/SER5:1)_48") (pintype "bidirectional"))
    )
    (net (code "75") (name "unconnected-(U3-PB08(AIN2{slash}SER4:0{slash}TC4:0)-Pad7)") (class "Default")
      (node (ref "U3") (pin "7") (pinfunction "PB08(AIN2/SER4:0/TC4:0)_7") (pintype "bidirectional"))
    )
    (net (code "76") (name "unconnected-(U3-PB10(SER4:2+)-Pad19)") (class "Default")
      (node (ref "U3") (pin "19") (pinfunction "PB10(SER4:2+)_19") (pintype "bidirectional"))
    )
    (net (code "77") (name "unconnected-(U3-PB11(SER4:3+)-Pad20)") (class "Default")
      (node (ref "U3") (pin "20") (pinfunction "PB11(SER4:3+)_20") (pintype "bidirectional"))
    )
    (net (code "78") (name "unconnected-(U4-BP-Pad4)") (class "Default")
      (node (ref "U4") (pin "4") (pinfunction "BP_4") (pintype "input"))
    )
  )
)
